# AUX_POWER_15V.net
KiCad netlist of a schematic drawn in Altium Designer
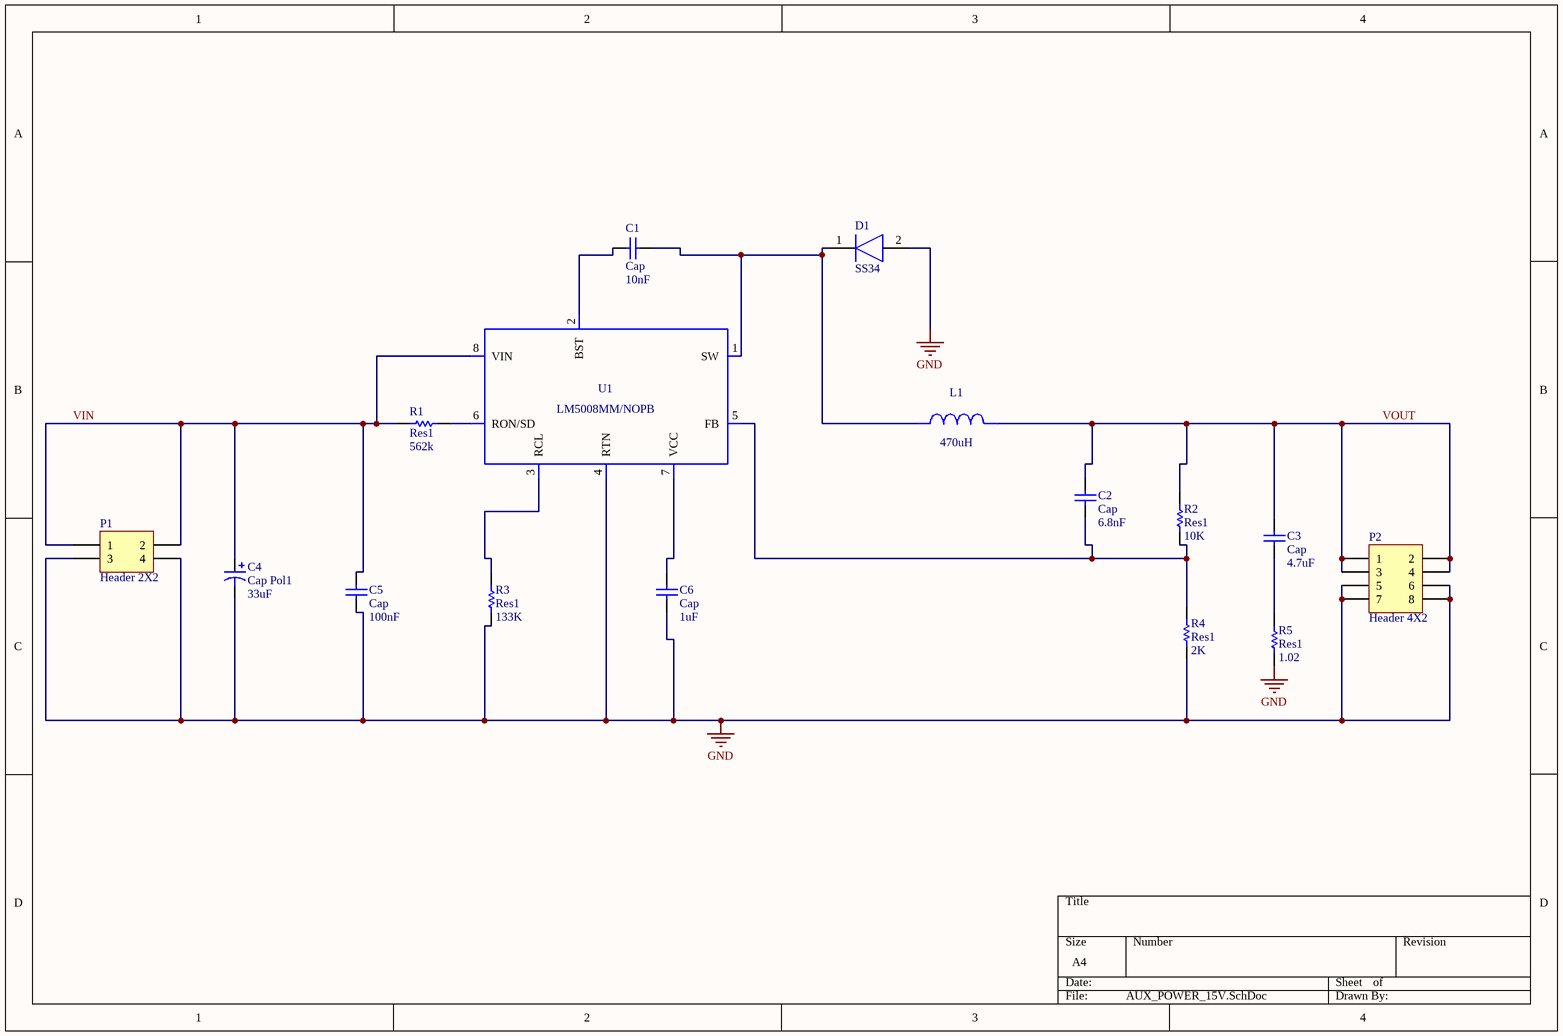
[diagram p0: AUX_POWER_15V.SchDoc]

(export (version "E")
  (design (tool "Eeschema 10.0.6"))
  (components
    (comp (ref "C1")
      (value "Cap")
      (footprint "C0805")
      (description "Capacitor")
      (fields (field (name "ALTIUM_VALUE") "10nF") (field (name "PUBLISHER") "Altium Limited"))
      (libsource (lib "Miscellaneous Devices") (part "Cap"))
    )
    (comp (ref "C2")
      (value "Cap")
      (footprint "C0805")
      (description "Capacitor")
      (fields (field (name "ALTIUM_VALUE") "6.8nF") (field (name "PUBLISHER") "Altium Limited"))
      (libsource (lib "Miscellaneous Devices") (part "Cap"))
    )
    (comp (ref "C3")
      (value "Cap")
      (footprint "C0805")
      (description "Capacitor")
      (fields (field (name "ALTIUM_VALUE") "4.7uF") (field (name "PUBLISHER") "Altium Limited"))
      (libsource (lib "Miscellaneous Devices") (part "Cap"))
    )
    (comp (ref "C4")
      (value "Cap Pol1")
      (footprint "C1206")
      (description "Polarized Capacitor (Radial)")
      (fields (field (name "ALTIUM_VALUE") "33uF") (field (name "PUBLISHER") "Altium Limited"))
      (libsource (lib "Miscellaneous Devices") (part "Cap Pol1"))
    )
    (comp (ref "C5")
      (value "Cap")
      (footprint "C0805")
      (description "Capacitor")
      (fields (field (name "ALTIUM_VALUE") "100nF") (field (name "PUBLISHER") "Altium Limited"))
      (libsource (lib "Miscellaneous Devices") (part "Cap"))
    )
    (comp (ref "C6")
      (value "Cap")
      (footprint "C0805")
      (description "Capacitor")
      (fields (field (name "ALTIUM_VALUE") "1uF") (field (name "PUBLISHER") "Altium Limited"))
      (libsource (lib "Miscellaneous Devices") (part "Cap"))
    )
    (comp (ref "D1")
      (value "SS34")
      (footprint "SamacSys:DIOM8059X265N")
      (description "Diode")
      (fields (field (name "MOUSER PART NUMBER") "512-SS34"))
      (libsource (lib "*") (part "SS34"))
    )
    (comp (ref "L1")
      (value "470uH")
      (footprint "INDUCTOR")
      (description "SRU1048-331Y")
      (libsource (lib "TI WEBENCH") (part "L1"))
    )
    (comp (ref "P1")
      (value "Header 2X2")
      (footprint "HDR2X2")
      (description "Header, 2-Pin, Dual row")
      (fields (field (name "PUBLISHER") "Altium Limited"))
      (libsource (lib "Miscellaneous Connectors") (part "Header 2X2"))
    )
    (comp (ref "P2")
      (value "Header 4X2")
      (footprint "HDR2X4")
      (description "Header, 4-Pin, Dual row")
      (fields (field (name "PUBLISHER") "Altium Limited"))
      (libsource (lib "Miscellaneous Connectors") (part "Header 4X2"))
    )
    (comp (ref "R1")
      (value "Res1")
      (footprint "1608[0603]")
      (description "Resistor")
      (fields (field (name "ALTIUM_VALUE") "562k") (field (name "PUBLISHER") "Altium Limited"))
      (libsource (lib "Miscellaneous Devices") (part "Res1"))
    )
    (comp (ref "R2")
      (value "Res1")
      (footprint "1608[0603]")
      (description "Resistor")
      (fields (field (name "ALTIUM_VALUE") "10K") (field (name "PUBLISHER") "Altium Limited"))
      (libsource (lib "Miscellaneous Devices") (part "Res1"))
    )
    (comp (ref "R3")
      (value "Res1")
      (footprint "1608[0603]")
      (description "Resistor")
      (fields (field (name "ALTIUM_VALUE") "133K") (field (name "PUBLISHER") "Altium Limited"))
      (libsource (lib "Miscellaneous Devices") (part "Res1"))
    )
    (comp (ref "R4")
      (value "Res1")
      (footprint "1608[0603]")
      (description "Resistor")
      (fields (field (name "ALTIUM_VALUE") "2K") (field (name "PUBLISHER") "Altium Limited"))
      (libsource (lib "Miscellaneous Devices") (part "Res1"))
    )
    (comp (ref "R5")
      (value "Res1")
      (footprint "1608[0603]")
      (description "Resistor")
      (fields (field (name "ALTIUM_VALUE") "1.02") (field (name "PUBLISHER") "Altium Limited"))
      (libsource (lib "Miscellaneous Devices") (part "Res1"))
    )
    (comp (ref "U1")
      (value "LM5008MM/NOPB")
      (footprint "SOIC127P600X175-8N")
      (fields (field (name "PACKAGEREFERENCE") "LM5008MM/NOPB"))
      (libsource (lib "TI WEBENCH") (part "U1"))
    )
  )
  (nets
    (net (code "1") (name "/VIN") (class "Default")
      (node (ref "C4") (pin "1") (pinfunction "1_1") (pintype "passive"))
      (node (ref "C5") (pin "2") (pinfunction "2_2") (pintype "passive"))
      (node (ref "P1") (pin "1") (pinfunction "1_1") (pintype "passive"))
      (node (ref "P1") (pin "2") (pinfunction "2_2") (pintype "passive"))
      (node (ref "R1") (pin "1") (pinfunction "1_1") (pintype "passive"))
      (node (ref "U1") (pin "8") (pinfunction "VIN_8") (pintype "passive"))
    )
    (net (code "2") (name "/VOUT") (class "Default")
      (node (ref "C2") (pin "2") (pinfunction "2_2") (pintype "passive"))
      (node (ref "C3") (pin "2") (pinfunction "2_2") (pintype "passive"))
      (node (ref "L1") (pin "2") (pinfunction "2_2") (pintype "passive"))
      (node (ref "P2") (pin "1") (pinfunction "1_1") (pintype "passive"))
      (node (ref "P2") (pin "2") (pinfunction "2_2") (pintype "passive"))
      (node (ref "P2") (pin "3") (pinfunction "3_3") (pintype "passive"))
      (node (ref "P2") (pin "4") (pinfunction "4_4") (pintype "passive"))
      (node (ref "R2") (pin "2") (pinfunction "2_2") (pintype "passive"))
    )
    (net (code "3") (name "GND") (class "Default")
      (node (ref "C4") (pin "2") (pinfunction "2_2") (pintype "passive"))
      (node (ref "C5") (pin "1") (pinfunction "1_1") (pintype "passive"))
      (node (ref "C6") (pin "1") (pinfunction "1_1") (pintype "passive"))
      (node (ref "D1") (pin "2") (pinfunction "A_2") (pintype "passive"))
      (node (ref "P1") (pin "3") (pinfunction "3_3") (pintype "passive"))
      (node (ref "P1") (pin "4") (pinfunction "4_4") (pintype "passive"))
      (node (ref "P2") (pin "5") (pinfunction "5_5") (pintype "passive"))
      (node (ref "P2") (pin "6") (pinfunction "6_6") (pintype "passive"))
      (node (ref "P2") (pin "7") (pinfunction "7_7") (pintype "passive"))
      (node (ref "P2") (pin "8") (pinfunction "8_8") (pintype "passive"))
      (node (ref "R3") (pin "1") (pinfunction "1_1") (pintype "passive"))
      (node (ref "R4") (pin "1") (pinfunction "1_1") (pintype "passive"))
      (node (ref "R5") (pin "1") (pinfunction "1_1") (pintype "passive"))
      (node (ref "U1") (pin "4") (pinfunction "RTN_4") (pintype "passive"))
    )
    (net (code "4") (name "Net-(C3-Pad1)") (class "Default")
      (node (ref "C3") (pin "1") (pinfunction "1_1") (pintype "passive"))
      (node (ref "R5") (pin "2") (pinfunction "2_2") (pintype "passive"))
    )
    (net (code "5") (name "Net-(D1-K)") (class "Default")
      (node (ref "C1") (pin "1") (pinfunction "1_1") (pintype "passive"))
      (node (ref "D1") (pin "1") (pinfunction "K_1") (pintype "passive"))
      (node (ref "L1") (pin "1") (pinfunction "1_1") (pintype "passive"))
      (node (ref "U1") (pin "1") (pinfunction "SW_1") (pintype "passive"))
    )
    (net (code "6") (name "Net-(U1-BST)") (class "Default")
      (node (ref "C1") (pin "2") (pinfunction "2_2") (pintype "passive"))
      (node (ref "U1") (pin "2") (pinfunction "BST_2") (pintype "passive"))
    )
    (net (code "7") (name "Net-(U1-FB)") (class "Default")
      (node (ref "C2") (pin "1") (pinfunction "1_1") (pintype "passive"))
      (node (ref "R2") (pin "1") (pinfunction "1_1") (pintype "passive"))
      (node (ref "R4") (pin "2") (pinfunction "2_2") (pintype "passive"))
      (node (ref "U1") (pin "5") (pinfunction "FB_5") (pintype "passive"))
    )
    (net (code "8") (name "Net-(U1-RCL)") (class "Default")
      (node (ref "R3") (pin "2") (pinfunction "2_2") (pintype "passive"))
      (node (ref "U1") (pin "3") (pinfunction "RCL_3") (pintype "passive"))
    )
    (net (code "9") (name "Net-(U1-RON{slash}SD)") (class "Default")
      (node (ref "R1") (pin "2") (pinfunction "2_2") (pintype "passive"))
      (node (ref "U1") (pin "6") (pinfunction "RON/SD_6") (pintype "passive"))
    )
    (net (code "10") (name "Net-(U1-VCC)") (class "Default")
      (node (ref "C6") (pin "2") (pinfunction "2_2") (pintype "passive"))
      (node (ref "U1") (pin "7") (pinfunction "VCC_7") (pintype "passive"))
    )
  )
)
